# throughhole.net
KiCad netlist of a schematic drawn in EAGLE
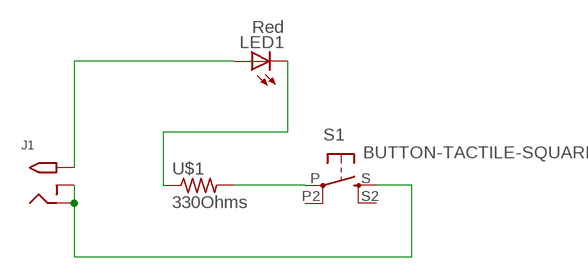
[diagram p0: schematic, sheet 1]

(export (version "E")
  (design (tool "Eeschema 10.0.6"))
  (components
    (comp (ref "J1")
      (value "2.1MMJACKTHM")
      (footprint "eagle-import:PJ-102A")
      (libsource (lib "eagle-import") (part "2.1MMJACKTHM"))
    )
    (comp (ref "LED1")
      (value "Red")
      (footprint "eagle-import:LED5MM")
      (libsource (lib "eagle-import") (part "LED5MM"))
    )
    (comp (ref "S1")
      (value "BUTTON-TACTILE-SQUARE")
      (footprint "eagle-import:BUTTON-TACTILE-SQUARE-ADAFRUIT1010")
      (libsource (lib "eagle-import") (part "BUTTON-TACTILE-SQUARE"))
    )
    (comp (ref "U$1")
      (value "330Ohms")
      (footprint "eagle-import:RESAD1160W55L680D260_HS")
      (libsource (lib "eagle-import") (part "RESISTORTH-1/4W-CARBON"))
    )
  )
  (nets
    (net (code "1") (name "Net-(J1-PadRING)") (class "Default")
      (node (ref "J1") (pin "RING") (pinfunction "RING_RING") (pintype "bidirectional"))
      (node (ref "J1") (pin "RING_SW") (pinfunction "RING_SW_RING_SW") (pintype "bidirectional"))
      (node (ref "S1") (pin "S") (pinfunction "S_S") (pintype "passive"))
    )
    (net (code "2") (name "Net-(J1-PadTIP)") (class "Default")
      (node (ref "J1") (pin "TIP") (pinfunction "TIP_TIP") (pintype "bidirectional"))
      (node (ref "LED1") (pin "A") (pinfunction "A_A") (pintype "passive"))
    )
    (net (code "3") (name "Net-(LED1-C)") (class "Default")
      (node (ref "LED1") (pin "K") (pinfunction "C_K") (pintype "passive"))
      (node (ref "U$1") (pin "1") (pinfunction "1_1") (pintype "passive"))
    )
    (net (code "4") (name "Net-(S1-PadP)") (class "Default")
      (node (ref "S1") (pin "P") (pinfunction "P_P") (pintype "passive"))
      (node (ref "U$1") (pin "2") (pinfunction "2_2") (pintype "passive"))
    )
    (net (code "5") (name "unconnected-(S1-P1-PadP2)") (class "Default")
      (node (ref "S1") (pin "P2") (pinfunction "P1_P2") (pintype "passive"))
    )
    (net (code "6") (name "unconnected-(S1-S1-PadS2)") (class "Default")
      (node (ref "S1") (pin "S2") (pinfunction "S1_S2") (pintype "passive"))
    )
  )
)
